# SEV-Remote-Control.net
KiCad netlist of a schematic drawn in EAGLE
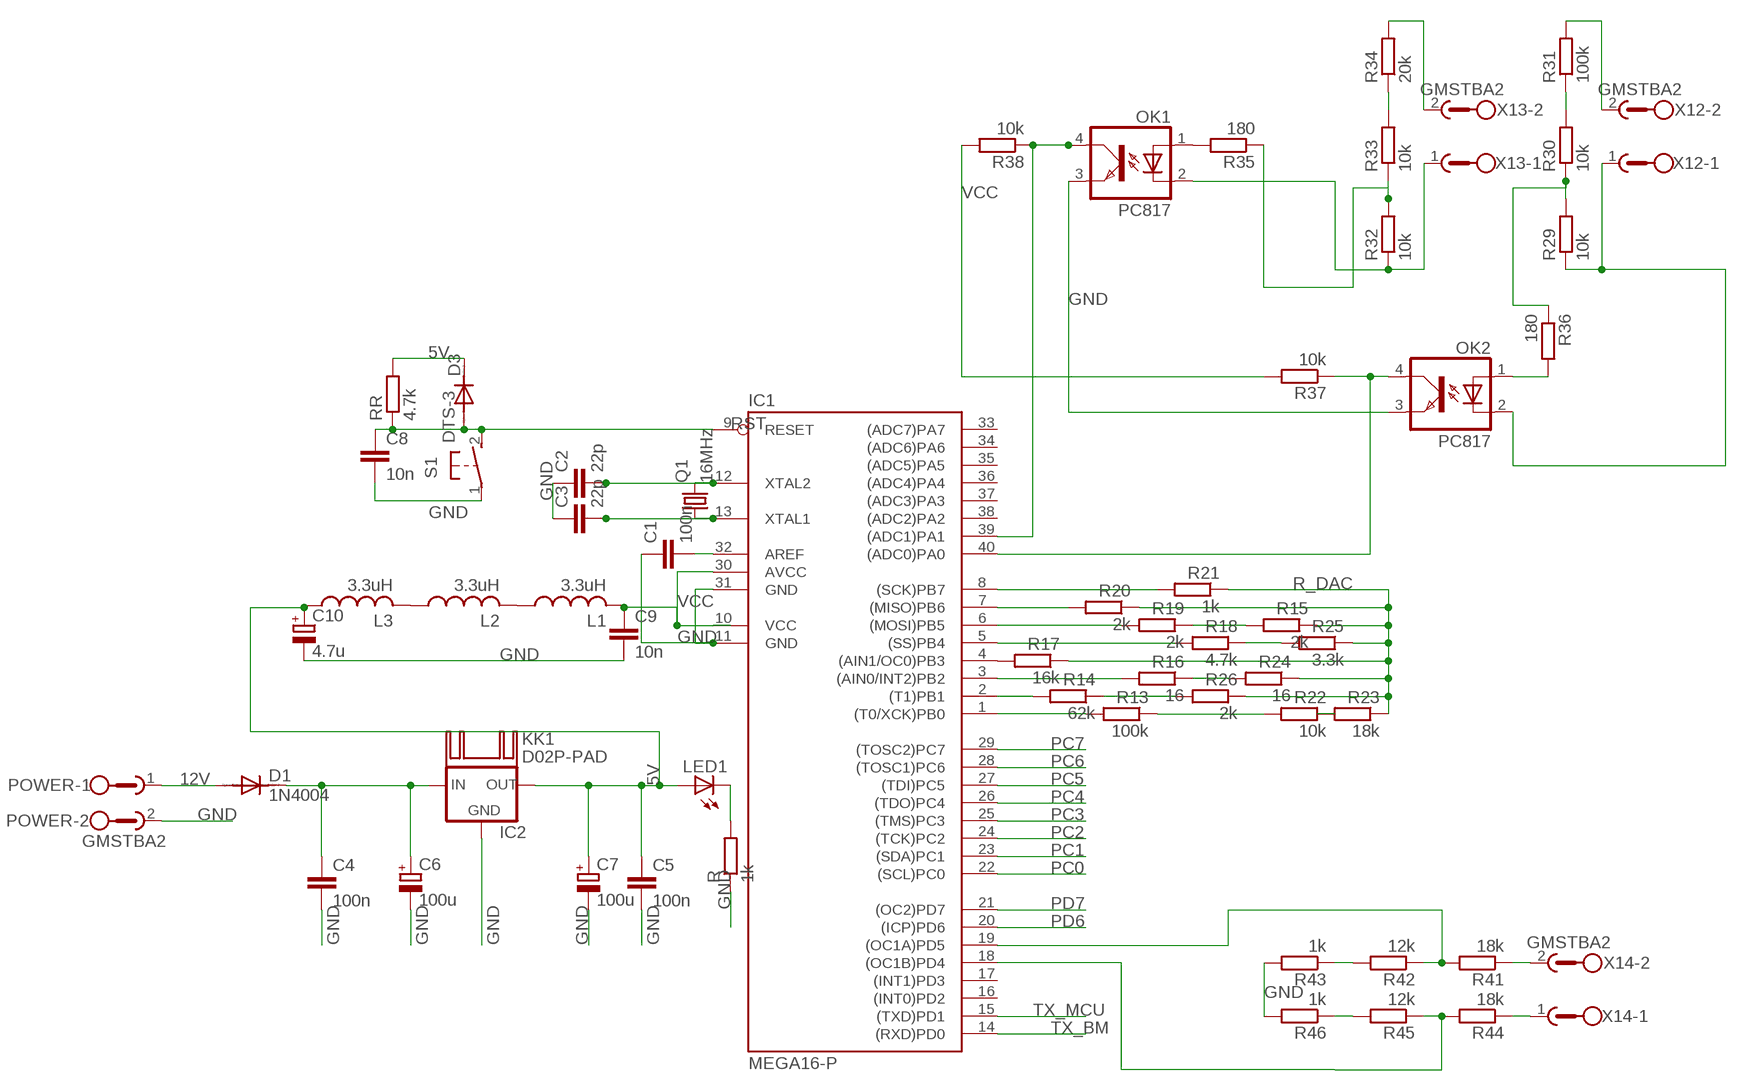
[diagram p0: schematic, sheet 1]
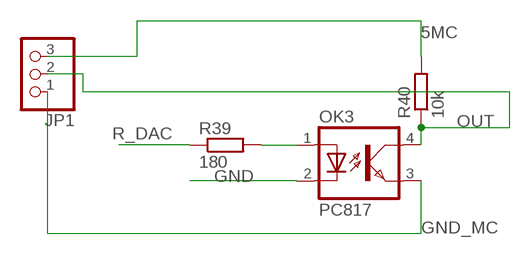
[diagram p1: schematic, sheet 2]
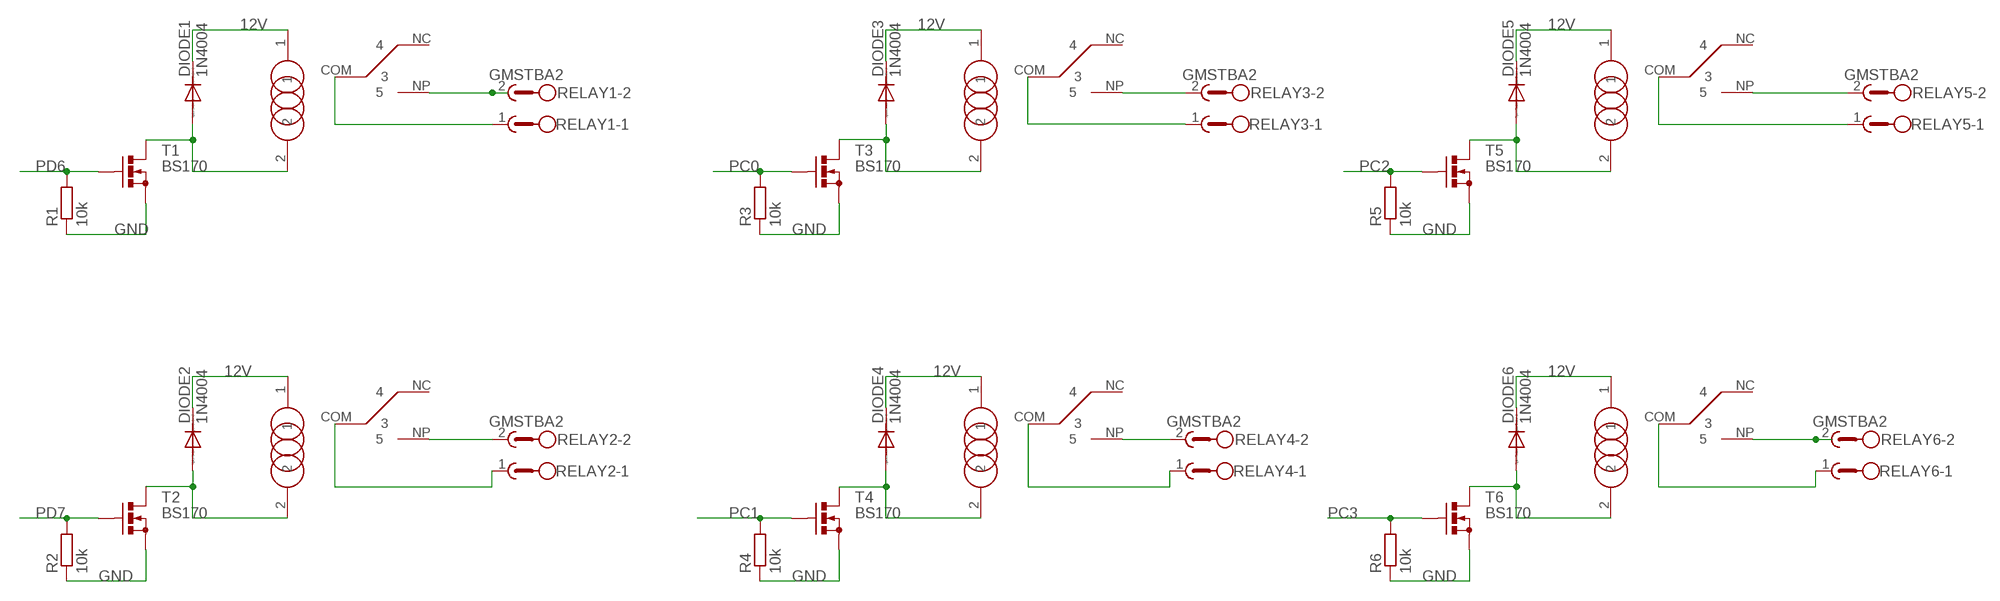
[diagram p2: schematic, sheet 3, part 1 of 2]
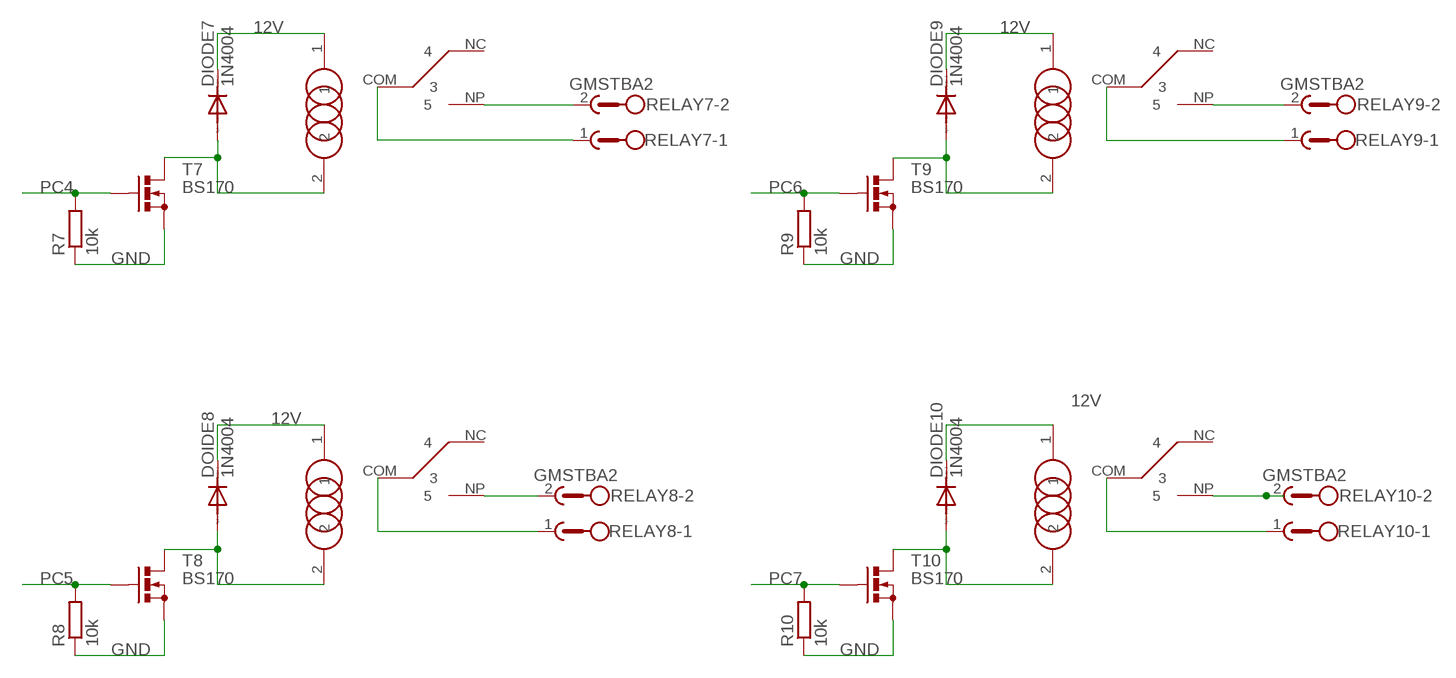
[diagram p3: schematic, sheet 3, part 2 of 2]
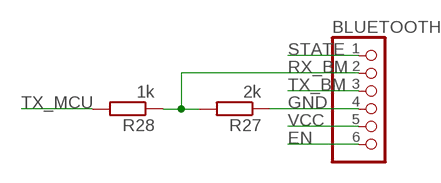
[diagram p4: schematic, sheet 4]

(export (version "E")
  (design (tool "Eeschema 10.0.6"))
  (components
    (comp (ref "C1")
      (value "100n")
      (footprint "eagle-import:C025-025X050")
      (libsource (lib "eagle-import") (part "C-EU025-025X050"))
    )
    (comp (ref "C2")
      (value "22p")
      (footprint "eagle-import:C025-025X050")
      (libsource (lib "eagle-import") (part "C-EU025-025X050"))
    )
    (comp (ref "C3")
      (value "22p")
      (footprint "eagle-import:C025-025X050")
      (libsource (lib "eagle-import") (part "C-EU025-025X050"))
    )
    (comp (ref "C4")
      (value "100n")
      (footprint "eagle-import:C025-025X050")
      (libsource (lib "eagle-import") (part "C-EU025-025X050"))
    )
    (comp (ref "C5")
      (value "100n")
      (footprint "eagle-import:C025-025X050")
      (libsource (lib "eagle-import") (part "C-EU025-025X050"))
    )
    (comp (ref "C6")
      (value "100u")
      (footprint "eagle-import:E2,5-6")
      (libsource (lib "eagle-import") (part "CPOL-EUE2.5-6"))
    )
    (comp (ref "C7")
      (value "100u")
      (footprint "eagle-import:E2,5-6")
      (libsource (lib "eagle-import") (part "CPOL-EUE2.5-6"))
    )
    (comp (ref "C8")
      (value "10n")
      (footprint "eagle-import:C025-025X050")
      (libsource (lib "eagle-import") (part "C-EU025-025X050"))
    )
    (comp (ref "C9")
      (value "10n")
      (footprint "eagle-import:C025-025X050")
      (libsource (lib "eagle-import") (part "C-EU025-025X050"))
    )
    (comp (ref "C10")
      (value "4.7u")
      (footprint "eagle-import:E2,5-6")
      (libsource (lib "eagle-import") (part "CPOL-EUE2.5-6"))
    )
    (comp (ref "D1")
      (value "1N4004")
      (footprint "eagle-import:DO41-10")
      (libsource (lib "eagle-import") (part "1N4004"))
    )
    (comp (ref "D3")
      (value "1N4148DO35-10")
      (footprint "eagle-import:DO35-10")
      (libsource (lib "eagle-import") (part "1N4148DO35-10"))
    )
    (comp (ref "IC1")
      (value "MEGA16-P")
      (footprint "eagle-import:DIL40")
      (fields (field (name "MPN") "ATMEGA16-16PU"))
      (libsource (lib "eagle-import") (part "MEGA16-P"))
    )
    (comp (ref "IC2")
      (value "78XXS")
      (footprint "eagle-import:78XXS")
      (libsource (lib "eagle-import") (part "78XXS"))
    )
    (comp (ref "KK1")
      (value "D02P-PAD")
      (footprint "eagle-import:D02PA-PAD")
      (libsource (lib "eagle-import") (part "D02P-PAD"))
    )
    (comp (ref "L1")
      (value "3.3uH")
      (footprint "eagle-import:0207_7")
      (libsource (lib "eagle-import") (part "L-US0207/7"))
    )
    (comp (ref "L2")
      (value "3.3uH")
      (footprint "eagle-import:0207_7")
      (libsource (lib "eagle-import") (part "L-US0207/7"))
    )
    (comp (ref "L3")
      (value "3.3uH")
      (footprint "eagle-import:0207_7")
      (libsource (lib "eagle-import") (part "L-US0207/7"))
    )
    (comp (ref "LED1")
      (value "LED5MM")
      (footprint "eagle-import:LED5MM")
      (libsource (lib "eagle-import") (part "LED5MM"))
    )
    (comp (ref "OK1")
      (value "PC817")
      (footprint "eagle-import:DIL04")
      (fields (field (name "MPN") "PC817X4J000F"))
      (libsource (lib "eagle-import") (part "PC817"))
    )
    (comp (ref "OK2")
      (value "PC817")
      (footprint "eagle-import:DIL04")
      (fields (field (name "MPN") "PC817X4J000F"))
      (libsource (lib "eagle-import") (part "PC817"))
    )
    (comp (ref "POWER")
      (value "GMSTBA2")
      (footprint "eagle-import:GMSTBA2")
      (fields (field (name "MF") "FARNELL") (field (name "MPN") "1757242"))
      (libsource (lib "eagle-import") (part "GMSTBA2"))
    )
    (comp (ref "Q1")
      (value "16MHz")
      (footprint "eagle-import:HC49_S")
      (libsource (lib "eagle-import") (part "CRYSTALHC49S"))
    )
    (comp (ref "R")
      (value "1k")
      (footprint "eagle-import:0207_10")
      (libsource (lib "eagle-import") (part "R-EU_0207/10"))
    )
    (comp (ref "R13")
      (value "100k")
      (footprint "eagle-import:0207_10")
      (libsource (lib "eagle-import") (part "R-EU_0207/10"))
    )
    (comp (ref "R14")
      (value "62k")
      (footprint "eagle-import:0207_10")
      (libsource (lib "eagle-import") (part "R-EU_0207/10"))
    )
    (comp (ref "R15")
      (value "2k")
      (footprint "eagle-import:0207_10")
      (libsource (lib "eagle-import") (part "R-EU_0207/10"))
    )
    (comp (ref "R16")
      (value "16")
      (footprint "eagle-import:0207_10")
      (libsource (lib "eagle-import") (part "R-EU_0207/10"))
    )
    (comp (ref "R17")
      (value "16k")
      (footprint "eagle-import:0207_10")
      (libsource (lib "eagle-import") (part "R-EU_0207/10"))
    )
    (comp (ref "R18")
      (value "4.7k")
      (footprint "eagle-import:0207_10")
      (libsource (lib "eagle-import") (part "R-EU_0207/10"))
    )
    (comp (ref "R19")
      (value "2k")
      (footprint "eagle-import:0207_10")
      (libsource (lib "eagle-import") (part "R-EU_0207/10"))
    )
    (comp (ref "R20")
      (value "2k")
      (footprint "eagle-import:0207_10")
      (libsource (lib "eagle-import") (part "R-EU_0207/10"))
    )
    (comp (ref "R21")
      (value "1k")
      (footprint "eagle-import:0207_10")
      (libsource (lib "eagle-import") (part "R-EU_0207/10"))
    )
    (comp (ref "R22")
      (value "10k")
      (footprint "eagle-import:0207_10")
      (libsource (lib "eagle-import") (part "R-EU_0207/10"))
    )
    (comp (ref "R23")
      (value "18k")
      (footprint "eagle-import:0207_10")
      (libsource (lib "eagle-import") (part "R-EU_0207/10"))
    )
    (comp (ref "R24")
      (value "16")
      (footprint "eagle-import:0207_10")
      (libsource (lib "eagle-import") (part "R-EU_0207/10"))
    )
    (comp (ref "R25")
      (value "3.3k")
      (footprint "eagle-import:0207_10")
      (libsource (lib "eagle-import") (part "R-EU_0207/10"))
    )
    (comp (ref "R26")
      (value "2k")
      (footprint "eagle-import:0207_10")
      (libsource (lib "eagle-import") (part "R-EU_0207/10"))
    )
    (comp (ref "R29")
      (value "10k")
      (footprint "eagle-import:0207_10")
      (libsource (lib "eagle-import") (part "R-EU_0207/10"))
    )
    (comp (ref "R30")
      (value "10k")
      (footprint "eagle-import:0207_10")
      (libsource (lib "eagle-import") (part "R-EU_0207/10"))
    )
    (comp (ref "R31")
      (value "100k")
      (footprint "eagle-import:0207_10")
      (libsource (lib "eagle-import") (part "R-EU_0207/10"))
    )
    (comp (ref "R32")
      (value "10k")
      (footprint "eagle-import:0207_10")
      (libsource (lib "eagle-import") (part "R-EU_0207/10"))
    )
    (comp (ref "R33")
      (value "10k")
      (footprint "eagle-import:0207_10")
      (libsource (lib "eagle-import") (part "R-EU_0207/10"))
    )
    (comp (ref "R34")
      (value "20k")
      (footprint "eagle-import:0207_10")
      (libsource (lib "eagle-import") (part "R-EU_0207/10"))
    )
    (comp (ref "R35")
      (value "180")
      (footprint "eagle-import:0207_10")
      (libsource (lib "eagle-import") (part "R-EU_0207/10"))
    )
    (comp (ref "R36")
      (value "180")
      (footprint "eagle-import:0207_10")
      (libsource (lib "eagle-import") (part "R-EU_0207/10"))
    )
    (comp (ref "R37")
      (value "10k")
      (footprint "eagle-import:0207_10")
      (libsource (lib "eagle-import") (part "R-EU_0207/10"))
    )
    (comp (ref "R38")
      (value "10k")
      (footprint "eagle-import:0207_10")
      (libsource (lib "eagle-import") (part "R-EU_0207/10"))
    )
    (comp (ref "R41")
      (value "18k")
      (footprint "eagle-import:0207_10")
      (libsource (lib "eagle-import") (part "R-EU_0207/10"))
    )
    (comp (ref "R42")
      (value "12k")
      (footprint "eagle-import:0207_10")
      (libsource (lib "eagle-import") (part "R-EU_0207/10"))
    )
    (comp (ref "R43")
      (value "1k")
      (footprint "eagle-import:0207_10")
      (libsource (lib "eagle-import") (part "R-EU_0207/10"))
    )
    (comp (ref "R44")
      (value "18k")
      (footprint "eagle-import:0207_10")
      (libsource (lib "eagle-import") (part "R-EU_0207/10"))
    )
    (comp (ref "R45")
      (value "12k")
      (footprint "eagle-import:0207_10")
      (libsource (lib "eagle-import") (part "R-EU_0207/10"))
    )
    (comp (ref "R46")
      (value "1k")
      (footprint "eagle-import:0207_10")
      (libsource (lib "eagle-import") (part "R-EU_0207/10"))
    )
    (comp (ref "RR")
      (value "4.7k")
      (footprint "eagle-import:0207_10")
      (libsource (lib "eagle-import") (part "R-EU_0207/10"))
    )
    (comp (ref "S1")
      (value "DTS-3")
      (footprint "eagle-import:DTS-3")
      (libsource (lib "eagle-import") (part "DTS-3"))
    )
    (comp (ref "X12")
      (value "GMSTBA2")
      (footprint "eagle-import:GMSTBA2")
      (fields (field (name "MF") "FARNELL") (field (name "MPN") "1757242"))
      (libsource (lib "eagle-import") (part "GMSTBA2"))
    )
    (comp (ref "X13")
      (value "GMSTBA2")
      (footprint "eagle-import:GMSTBA2")
      (fields (field (name "MF") "FARNELL") (field (name "MPN") "1757242"))
      (libsource (lib "eagle-import") (part "GMSTBA2"))
    )
    (comp (ref "X14")
      (value "GMSTBA2")
      (footprint "eagle-import:GMSTBA2")
      (fields (field (name "MF") "FARNELL") (field (name "MPN") "1757242"))
      (libsource (lib "eagle-import") (part "GMSTBA2"))
    )
    (comp (ref "BLUETOOTH")
      (value "PINHD-1X6")
      (footprint "eagle-import:1X06")
      (libsource (lib "eagle-import") (part "PINHD-1X6"))
    )
    (comp (ref "R27")
      (value "2k")
      (footprint "eagle-import:0207_10")
      (libsource (lib "eagle-import") (part "R-EU_0207/10"))
    )
    (comp (ref "R28")
      (value "1k")
      (footprint "eagle-import:0207_10")
      (libsource (lib "eagle-import") (part "R-EU_0207/10"))
    )
    (comp (ref "JP1")
      (value "PINHD-1X3")
      (footprint "eagle-import:1X03")
      (libsource (lib "eagle-import") (part "PINHD-1X3"))
    )
    (comp (ref "OK3")
      (value "PC817")
      (footprint "eagle-import:DIL04")
      (fields (field (name "MPN") "PC817X4J000F"))
      (libsource (lib "eagle-import") (part "PC817"))
    )
    (comp (ref "R39")
      (value "180")
      (footprint "eagle-import:0207_10")
      (libsource (lib "eagle-import") (part "R-EU_0207/10"))
    )
    (comp (ref "R40")
      (value "10k")
      (footprint "eagle-import:0207_10")
      (libsource (lib "eagle-import") (part "R-EU_0207/10"))
    )
    (comp (ref "DIODE1")
      (value "1N4004")
      (footprint "eagle-import:DO41-10")
      (libsource (lib "eagle-import") (part "1N4004"))
    )
    (comp (ref "DIODE2")
      (value "1N4004")
      (footprint "eagle-import:DO41-10")
      (libsource (lib "eagle-import") (part "1N4004"))
    )
    (comp (ref "DIODE3")
      (value "1N4004")
      (footprint "eagle-import:DO41-10")
      (libsource (lib "eagle-import") (part "1N4004"))
    )
    (comp (ref "DIODE4")
      (value "1N4004")
      (footprint "eagle-import:DO41-10")
      (libsource (lib "eagle-import") (part "1N4004"))
    )
    (comp (ref "DIODE5")
      (value "1N4004")
      (footprint "eagle-import:DO41-10")
      (libsource (lib "eagle-import") (part "1N4004"))
    )
    (comp (ref "DIODE6")
      (value "1N4004")
      (footprint "eagle-import:DO41-10")
      (libsource (lib "eagle-import") (part "1N4004"))
    )
    (comp (ref "DIODE7")
      (value "1N4004")
      (footprint "eagle-import:DO41-10")
      (libsource (lib "eagle-import") (part "1N4004"))
    )
    (comp (ref "DIODE9")
      (value "1N4004")
      (footprint "eagle-import:DO41-10")
      (libsource (lib "eagle-import") (part "1N4004"))
    )
    (comp (ref "DIODE10")
      (value "1N4004")
      (footprint "eagle-import:DO41-10")
      (libsource (lib "eagle-import") (part "1N4004"))
    )
    (comp (ref "DOIDE8")
      (value "1N4004")
      (footprint "eagle-import:DO41-10")
      (libsource (lib "eagle-import") (part "1N4004"))
    )
    (comp (ref "R1")
      (value "10k")
      (footprint "eagle-import:0207_10")
      (libsource (lib "eagle-import") (part "R-EU_0207/10"))
    )
    (comp (ref "R2")
      (value "10k")
      (footprint "eagle-import:0207_10")
      (libsource (lib "eagle-import") (part "R-EU_0207/10"))
    )
    (comp (ref "R3")
      (value "10k")
      (footprint "eagle-import:0207_10")
      (libsource (lib "eagle-import") (part "R-EU_0207/10"))
    )
    (comp (ref "R4")
      (value "10k")
      (footprint "eagle-import:0207_10")
      (libsource (lib "eagle-import") (part "R-EU_0207/10"))
    )
    (comp (ref "R5")
      (value "10k")
      (footprint "eagle-import:0207_10")
      (libsource (lib "eagle-import") (part "R-EU_0207/10"))
    )
    (comp (ref "R6")
      (value "10k")
      (footprint "eagle-import:0207_10")
      (libsource (lib "eagle-import") (part "R-EU_0207/10"))
    )
    (comp (ref "R7")
      (value "10k")
      (footprint "eagle-import:0207_10")
      (libsource (lib "eagle-import") (part "R-EU_0207/10"))
    )
    (comp (ref "R8")
      (value "10k")
      (footprint "eagle-import:0207_10")
      (libsource (lib "eagle-import") (part "R-EU_0207/10"))
    )
    (comp (ref "R9")
      (value "10k")
      (footprint "eagle-import:0207_10")
      (libsource (lib "eagle-import") (part "R-EU_0207/10"))
    )
    (comp (ref "R10")
      (value "10k")
      (footprint "eagle-import:0207_10")
      (libsource (lib "eagle-import") (part "R-EU_0207/10"))
    )
    (comp (ref "REL3")
      (value "RELAY")
      (footprint "eagle-import:RELAY")
      (libsource (lib "eagle-import") (part "RELAY"))
    )
    (comp (ref "RELAY1")
      (value "GMSTBA2")
      (footprint "eagle-import:GMSTBA2")
      (fields (field (name "MF") "FARNELL") (field (name "MPN") "1757242"))
      (libsource (lib "eagle-import") (part "GMSTBA2"))
    )
    (comp (ref "RELAY2")
      (value "GMSTBA2")
      (footprint "eagle-import:GMSTBA2")
      (fields (field (name "MF") "FARNELL") (field (name "MPN") "1757242"))
      (libsource (lib "eagle-import") (part "GMSTBA2"))
    )
    (comp (ref "RELAY3")
      (value "GMSTBA2")
      (footprint "eagle-import:GMSTBA2")
      (fields (field (name "MF") "FARNELL") (field (name "MPN") "1757242"))
      (libsource (lib "eagle-import") (part "GMSTBA2"))
    )
    (comp (ref "RELAY4")
      (value "GMSTBA2")
      (footprint "eagle-import:GMSTBA2")
      (fields (field (name "MF") "FARNELL") (field (name "MPN") "1757242"))
      (libsource (lib "eagle-import") (part "GMSTBA2"))
    )
    (comp (ref "RELAY5")
      (value "GMSTBA2")
      (footprint "eagle-import:GMSTBA2")
      (fields (field (name "MF") "FARNELL") (field (name "MPN") "1757242"))
      (libsource (lib "eagle-import") (part "GMSTBA2"))
    )
    (comp (ref "RELAY6")
      (value "GMSTBA2")
      (footprint "eagle-import:GMSTBA2")
      (fields (field (name "MF") "FARNELL") (field (name "MPN") "1757242"))
      (libsource (lib "eagle-import") (part "GMSTBA2"))
    )
    (comp (ref "RELAY7")
      (value "GMSTBA2")
      (footprint "eagle-import:GMSTBA2")
      (fields (field (name "MF") "FARNELL") (field (name "MPN") "1757242"))
      (libsource (lib "eagle-import") (part "GMSTBA2"))
    )
    (comp (ref "RELAY8")
      (value "GMSTBA2")
      (footprint "eagle-import:GMSTBA2")
      (fields (field (name "MF") "FARNELL") (field (name "MPN") "1757242"))
      (libsource (lib "eagle-import") (part "GMSTBA2"))
    )
    (comp (ref "RELAY9")
      (value "GMSTBA2")
      (footprint "eagle-import:GMSTBA2")
      (fields (field (name "MF") "FARNELL") (field (name "MPN") "1757242"))
      (libsource (lib "eagle-import") (part "GMSTBA2"))
    )
    (comp (ref "RELAY10")
      (value "GMSTBA2")
      (footprint "eagle-import:GMSTBA2")
      (fields (field (name "MF") "FARNELL") (field (name "MPN") "1757242"))
      (libsource (lib "eagle-import") (part "GMSTBA2"))
    )
    (comp (ref "T1")
      (value "BS170")
      (footprint "eagle-import:SOT54E")
      (libsource (lib "eagle-import") (part "BS170"))
    )
    (comp (ref "T2")
      (value "BS170")
      (footprint "eagle-import:SOT54E")
      (libsource (lib "eagle-import") (part "BS170"))
    )
    (comp (ref "T3")
      (value "BS170")
      (footprint "eagle-import:SOT54E")
      (libsource (lib "eagle-import") (part "BS170"))
    )
    (comp (ref "T4")
      (value "BS170")
      (footprint "eagle-import:SOT54E")
      (libsource (lib "eagle-import") (part "BS170"))
    )
    (comp (ref "T5")
      (value "BS170")
      (footprint "eagle-import:SOT54E")
      (libsource (lib "eagle-import") (part "BS170"))
    )
    (comp (ref "T6")
      (value "BS170")
      (footprint "eagle-import:SOT54E")
      (libsource (lib "eagle-import") (part "BS170"))
    )
    (comp (ref "T7")
      (value "BS170")
      (footprint "eagle-import:SOT54E")
      (libsource (lib "eagle-import") (part "BS170"))
    )
    (comp (ref "T8")
      (value "BS170")
      (footprint "eagle-import:SOT54E")
      (libsource (lib "eagle-import") (part "BS170"))
    )
    (comp (ref "T9")
      (value "BS170")
      (footprint "eagle-import:SOT54E")
      (libsource (lib "eagle-import") (part "BS170"))
    )
    (comp (ref "T10")
      (value "BS170")
      (footprint "eagle-import:SOT54E")
      (libsource (lib "eagle-import") (part "BS170"))
    )
    (comp (ref "U$1")
      (value "RELAY")
      (footprint "eagle-import:RELAY")
      (libsource (lib "eagle-import") (part "RELAY"))
    )
    (comp (ref "U$2")
      (value "RELAY")
      (footprint "eagle-import:RELAY")
      (libsource (lib "eagle-import") (part "RELAY"))
    )
    (comp (ref "U$3")
      (value "RELAY")
      (footprint "eagle-import:RELAY")
      (libsource (lib "eagle-import") (part "RELAY"))
    )
    (comp (ref "U$5")
      (value "RELAY")
      (footprint "eagle-import:RELAY")
      (libsource (lib "eagle-import") (part "RELAY"))
    )
    (comp (ref "U$6")
      (value "RELAY")
      (footprint "eagle-import:RELAY")
      (libsource (lib "eagle-import") (part "RELAY"))
    )
    (comp (ref "U$7")
      (value "RELAY")
      (footprint "eagle-import:RELAY")
      (libsource (lib "eagle-import") (part "RELAY"))
    )
    (comp (ref "U$8")
      (value "RELAY")
      (footprint "eagle-import:RELAY")
      (libsource (lib "eagle-import") (part "RELAY"))
    )
    (comp (ref "U$9")
      (value "RELAY")
      (footprint "eagle-import:RELAY")
      (libsource (lib "eagle-import") (part "RELAY"))
    )
    (comp (ref "U$10")
      (value "RELAY")
      (footprint "eagle-import:RELAY")
      (libsource (lib "eagle-import") (part "RELAY"))
    )
  )
  (nets
    (net (code "1") (name "5MC") (class "Default")
      (node (ref "JP1") (pin "3") (pinfunction "3_3") (pintype "passive"))
      (node (ref "R40") (pin "2") (pinfunction "2_2") (pintype "passive"))
    )
    (net (code "2") (name "5V") (class "Default")
      (node (ref "C10") (pin "+") (pinfunction "+_+") (pintype "passive"))
      (node (ref "C5") (pin "1") (pinfunction "1_1") (pintype "passive"))
      (node (ref "C7") (pin "+") (pinfunction "+_+") (pintype "passive"))
      (node (ref "D3") (pin "C") (pinfunction "C_C") (pintype "passive"))
      (node (ref "IC2") (pin "OUT") (pinfunction "OUT_OUT") (pintype "passive"))
      (node (ref "L3") (pin "1") (pinfunction "1_1") (pintype "passive"))
      (node (ref "LED1") (pin "A") (pinfunction "A_A") (pintype "passive"))
      (node (ref "RR") (pin "2") (pinfunction "2_2") (pintype "passive"))
    )
    (net (code "3") (name "12V") (class "Default")
      (node (ref "D1") (pin "A") (pinfunction "A_A") (pintype "passive"))
      (node (ref "DIODE1") (pin "C") (pinfunction "C_C") (pintype "passive"))
      (node (ref "DIODE10") (pin "C") (pinfunction "C_C") (pintype "passive"))
      (node (ref "DIODE2") (pin "C") (pinfunction "C_C") (pintype "passive"))
      (node (ref "DIODE3") (pin "C") (pinfunction "C_C") (pintype "passive"))
      (node (ref "DIODE4") (pin "C") (pinfunction "C_C") (pintype "passive"))
      (node (ref "DIODE5") (pin "C") (pinfunction "C_C") (pintype "passive"))
      (node (ref "DIODE6") (pin "C") (pinfunction "C_C") (pintype "passive"))
      (node (ref "DIODE7") (pin "C") (pinfunction "C_C") (pintype "passive"))
      (node (ref "DIODE9") (pin "C") (pinfunction "C_C") (pintype "passive"))
      (node (ref "DOIDE8") (pin "C") (pinfunction "C_C") (pintype "passive"))
      (node (ref "POWER") (pin "1") (pinfunction "1_1") (pintype "passive"))
      (node (ref "REL3") (pin "1") (pinfunction "1_1") (pintype "bidirectional"))
      (node (ref "U$1") (pin "1") (pinfunction "1_1") (pintype "bidirectional"))
      (node (ref "U$10") (pin "1") (pinfunction "1_1") (pintype "bidirectional"))
      (node (ref "U$2") (pin "1") (pinfunction "1_1") (pintype "bidirectional"))
      (node (ref "U$3") (pin "1") (pinfunction "1_1") (pintype "bidirectional"))
      (node (ref "U$5") (pin "1") (pinfunction "1_1") (pintype "bidirectional"))
      (node (ref "U$6") (pin "1") (pinfunction "1_1") (pintype "bidirectional"))
      (node (ref "U$7") (pin "1") (pinfunction "1_1") (pintype "bidirectional"))
      (node (ref "U$8") (pin "1") (pinfunction "1_1") (pintype "bidirectional"))
      (node (ref "U$9") (pin "1") (pinfunction "1_1") (pintype "bidirectional"))
    )
    (net (code "4") (name "EN") (class "Default")
      (node (ref "BLUETOOTH") (pin "6") (pinfunction "6_6") (pintype "passive"))
    )
    (net (code "5") (name "GND") (class "Default")
      (node (ref "BLUETOOTH") (pin "4") (pinfunction "4_4") (pintype "passive"))
      (node (ref "C1") (pin "1") (pinfunction "1_1") (pintype "passive"))
      (node (ref "C10") (pin "-") (pinfunction "-_-") (pintype "passive"))
      (node (ref "C2") (pin "1") (pinfunction "1_1") (pintype "passive"))
      (node (ref "C3") (pin "1") (pinfunction "1_1") (pintype "passive"))
      (node (ref "C4") (pin "2") (pinfunction "2_2") (pintype "passive"))
      (node (ref "C5") (pin "2") (pinfunction "2_2") (pintype "passive"))
      (node (ref "C6") (pin "-") (pinfunction "-_-") (pintype "passive"))
      (node (ref "C7") (pin "-") (pinfunction "-_-") (pintype "passive"))
      (node (ref "C8") (pin "2") (pinfunction "2_2") (pintype "passive"))
      (node (ref "C9") (pin "2") (pinfunction "2_2") (pintype "passive"))
      (node (ref "IC1") (pin "11") (pinfunction "GND_11") (pintype "power_in"))
      (node (ref "IC1") (pin "31") (pinfunction "GND_31") (pintype "power_in"))
      (node (ref "IC2") (pin "GND") (pinfunction "GND_GND") (pintype "input"))
      (node (ref "OK1") (pin "3") (pinfunction "EMIT_3") (pintype "passive"))
      (node (ref "OK2") (pin "3") (pinfunction "EMIT_3") (pintype "passive"))
      (node (ref "OK3") (pin "2") (pinfunction "C_2") (pintype "passive"))
      (node (ref "POWER") (pin "2") (pinfunction "1_2") (pintype "passive"))
      (node (ref "R") (pin "1") (pinfunction "1_1") (pintype "passive"))
      (node (ref "R1") (pin "1") (pinfunction "1_1") (pintype "passive"))
      (node (ref "R10") (pin "1") (pinfunction "1_1") (pintype "passive"))
      (node (ref "R2") (pin "1") (pinfunction "1_1") (pintype "passive"))
      (node (ref "R27") (pin "1") (pinfunction "1_1") (pintype "passive"))
      (node (ref "R3") (pin "1") (pinfunction "1_1") (pintype "passive"))
      (node (ref "R4") (pin "1") (pinfunction "1_1") (pintype "passive"))
      (node (ref "R43") (pin "2") (pinfunction "2_2") (pintype "passive"))
      (node (ref "R46") (pin "2") (pinfunction "2_2") (pintype "passive"))
      (node (ref "R5") (pin "1") (pinfunction "1_1") (pintype "passive"))
      (node (ref "R6") (pin "1") (pinfunction "1_1") (pintype "passive"))
      (node (ref "R7") (pin "1") (pinfunction "1_1") (pintype "passive"))
      (node (ref "R8") (pin "1") (pinfunction "1_1") (pintype "passive"))
      (node (ref "R9") (pin "1") (pinfunction "1_1") (pintype "passive"))
      (node (ref "S1") (pin "1") (pinfunction "1_1") (pintype "passive"))
      (node (ref "T1") (pin "S") (pinfunction "S_S") (pintype "passive"))
      (node (ref "T10") (pin "S") (pinfunction "S_S") (pintype "passive"))
      (node (ref "T2") (pin "S") (pinfunction "S_S") (pintype "passive"))
      (node (ref "T3") (pin "S") (pinfunction "S_S") (pintype "passive"))
      (node (ref "T4") (pin "S") (pinfunction "S_S") (pintype "passive"))
      (node (ref "T5") (pin "S") (pinfunction "S_S") (pintype "passive"))
      (node (ref "T6") (pin "S") (pinfunction "S_S") (pintype "passive"))
      (node (ref "T7") (pin "S") (pinfunction "S_S") (pintype "passive"))
      (node (ref "T8") (pin "S") (pinfunction "S_S") (pintype "passive"))
      (node (ref "T9") (pin "S") (pinfunction "S_S") (pintype "passive"))
    )
    (net (code "6") (name "GND_MC") (class "Default")
      (node (ref "JP1") (pin "1") (pinfunction "1_1") (pintype "passive"))
      (node (ref "OK3") (pin "3") (pinfunction "EMIT_3") (pintype "passive"))
    )
    (net (code "7") (name "Net-(C4-Pad1)") (class "Default")
      (node (ref "C4") (pin "1") (pinfunction "1_1") (pintype "passive"))
      (node (ref "C6") (pin "+") (pinfunction "+_+") (pintype "passive"))
      (node (ref "D1") (pin "C") (pinfunction "C_C") (pintype "passive"))
      (node (ref "IC2") (pin "IN") (pinfunction "IN_IN") (pintype "input"))
    )
    (net (code "8") (name "Net-(DIODE1-PadA)") (class "Default")
      (node (ref "DIODE1") (pin "A") (pinfunction "A_A") (pintype "passive"))
      (node (ref "T1") (pin "D") (pinfunction "D_D") (pintype "passive"))
      (node (ref "U$7") (pin "2") (pinfunction "2_2") (pintype "bidirectional"))
    )
    (net (code "9") (name "Net-(DIODE2-PadA)") (class "Default")
      (node (ref "DIODE2") (pin "A") (pinfunction "A_A") (pintype "passive"))
      (node (ref "T2") (pin "D") (pinfunction "D_D") (pintype "passive"))
      (node (ref "U$9") (pin "2") (pinfunction "2_2") (pintype "bidirectional"))
    )
    (net (code "10") (name "Net-(DIODE3-PadA)") (class "Default")
      (node (ref "DIODE3") (pin "A") (pinfunction "A_A") (pintype "passive"))
      (node (ref "REL3") (pin "2") (pinfunction "2_2") (pintype "bidirectional"))
      (node (ref "T3") (pin "D") (pinfunction "D_D") (pintype "passive"))
    )
    (net (code "11") (name "Net-(DIODE4-PadA)") (class "Default")
      (node (ref "DIODE4") (pin "A") (pinfunction "A_A") (pintype "passive"))
      (node (ref "T4") (pin "D") (pinfunction "D_D") (pintype "passive"))
      (node (ref "U$5") (pin "2") (pinfunction "2_2") (pintype "bidirectional"))
    )
    (net (code "12") (name "Net-(DIODE5-PadA)") (class "Default")
      (node (ref "DIODE5") (pin "A") (pinfunction "A_A") (pintype "passive"))
      (node (ref "T5") (pin "D") (pinfunction "D_D") (pintype "passive"))
      (node (ref "U$6") (pin "2") (pinfunction "2_2") (pintype "bidirectional"))
    )
    (net (code "13") (name "Net-(DIODE6-PadA)") (class "Default")
      (node (ref "DIODE6") (pin "A") (pinfunction "A_A") (pintype "passive"))
      (node (ref "T6") (pin "D") (pinfunction "D_D") (pintype "passive"))
      (node (ref "U$8") (pin "2") (pinfunction "2_2") (pintype "bidirectional"))
    )
    (net (code "14") (name "Net-(DIODE7-PadA)") (class "Default")
      (node (ref "DIODE7") (pin "A") (pinfunction "A_A") (pintype "passive"))
      (node (ref "T7") (pin "D") (pinfunction "D_D") (pintype "passive"))
      (node (ref "U$10") (pin "2") (pinfunction "2_2") (pintype "bidirectional"))
    )
    (net (code "15") (name "Net-(DIODE9-PadA)") (class "Default")
      (node (ref "DIODE9") (pin "A") (pinfunction "A_A") (pintype "passive"))
      (node (ref "T9") (pin "D") (pinfunction "D_D") (pintype "passive"))
      (node (ref "U$2") (pin "2") (pinfunction "2_2") (pintype "bidirectional"))
    )
    (net (code "16") (name "Net-(DIODE10-PadA)") (class "Default")
      (node (ref "DIODE10") (pin "A") (pinfunction "A_A") (pintype "passive"))
      (node (ref "T10") (pin "D") (pinfunction "D_D") (pintype "passive"))
      (node (ref "U$3") (pin "2") (pinfunction "2_2") (pintype "bidirectional"))
    )
    (net (code "17") (name "Net-(DOIDE8-PadA)") (class "Default")
      (node (ref "DOIDE8") (pin "A") (pinfunction "A_A") (pintype "passive"))
      (node (ref "T8") (pin "D") (pinfunction "D_D") (pintype "passive"))
      (node (ref "U$1") (pin "2") (pinfunction "2_2") (pintype "bidirectional"))
    )
    (net (code "18") (name "Net-(IC1-(ADC0)PA0)") (class "Default")
      (node (ref "IC1") (pin "40") (pinfunction "(ADC0)PA0_40") (pintype "bidirectional"))
      (node (ref "OK2") (pin "4") (pinfunction "COL_4") (pintype "passive"))
      (node (ref "R37") (pin "1") (pinfunction "1_1") (pintype "passive"))
    )
    (net (code "19") (name "Net-(IC1-(ADC1)PA1)") (class "Default")
      (node (ref "IC1") (pin "39") (pinfunction "(ADC1)PA1_39") (pintype "bidirectional"))
      (node (ref "OK1") (pin "4") (pinfunction "COL_4") (pintype "passive"))
      (node (ref "R38") (pin "1") (pinfunction "1_1") (pintype "passive"))
    )
    (net (code "20") (name "Net-(IC1-(AIN0{slash}INT2)PB2)") (class "Default")
      (node (ref "IC1") (pin "3") (pinfunction "(AIN0/INT2)PB2_3") (pintype "bidirectional"))
      (node (ref "R16") (pin "2") (pinfunction "2_2") (pintype "passive"))
    )
    (net (code "21") (name "Net-(IC1-(AIN1{slash}OC0)PB3)") (class "Default")
      (node (ref "IC1") (pin "4") (pinfunction "(AIN1/OC0)PB3_4") (pintype "bidirectional"))
      (node (ref "R17") (pin "2") (pinfunction "2_2") (pintype "passive"))
    )
    (net (code "22") (name "Net-(IC1-(MISO)PB6)") (class "Default")
      (node (ref "IC1") (pin "7") (pinfunction "(MISO)PB6_7") (pintype "bidirectional"))
      (node (ref "R20") (pin "2") (pinfunction "2_2") (pintype "passive"))
    )
    (net (code "23") (name "Net-(IC1-(MOSI)PB5)") (class "Default")
      (node (ref "IC1") (pin "6") (pinfunction "(MOSI)PB5_6") (pintype "bidirectional"))
      (node (ref "R19") (pin "2") (pinfunction "2_2") (pintype "passive"))
    )
    (net (code "24") (name "Net-(IC1-(OC1A)PD5)") (class "Default")
      (node (ref "IC1") (pin "19") (pinfunction "(OC1A)PD5_19") (pintype "bidirectional"))
      (node (ref "R41") (pin "2") (pinfunction "2_2") (pintype "passive"))
      (node (ref "R42") (pin "1") (pinfunction "1_1") (pintype "passive"))
    )
    (net (code "25") (name "Net-(IC1-(OC1B)PD4)") (class "Default")
      (node (ref "IC1") (pin "18") (pinfunction "(OC1B)PD4_18") (pintype "bidirectional"))
      (node (ref "R44") (pin "2") (pinfunction "2_2") (pintype "passive"))
      (node (ref "R45") (pin "1") (pinfunction "1_1") (pintype "passive"))
    )
    (net (code "26") (name "Net-(IC1-(SCK)PB7)") (class "Default")
      (node (ref "IC1") (pin "8") (pinfunction "(SCK)PB7_8") (pintype "bidirectional"))
      (node (ref "R21") (pin "2") (pinfunction "2_2") (pintype "passive"))
    )
    (net (code "27") (name "Net-(IC1-(SS)PB4)") (class "Default")
      (node (ref "IC1") (pin "5") (pinfunction "(SS)PB4_5") (pintype "bidirectional"))
      (node (ref "R18") (pin "2") (pinfunction "2_2") (pintype "passive"))
    )
    (net (code "28") (name "Net-(IC1-(T0{slash}XCK)PB0)") (class "Default")
      (node (ref "IC1") (pin "1") (pinfunction "(T0/XCK)PB0_1") (pintype "bidirectional"))
      (node (ref "R13") (pin "2") (pinfunction "2_2") (pintype "passive"))
    )
    (net (code "29") (name "Net-(IC1-(T1)PB1)") (class "Default")
      (node (ref "IC1") (pin "2") (pinfunction "(T1)PB1_2") (pintype "bidirectional"))
      (node (ref "R14") (pin "2") (pinfunction "2_2") (pintype "passive"))
    )
    (net (code "30") (name "Net-(IC1-AREF)") (class "Default")
      (node (ref "C1") (pin "2") (pinfunction "2_2") (pintype "passive"))
      (node (ref "IC1") (pin "32") (pinfunction "AREF_32") (pintype "passive"))
    )
    (net (code "31") (name "Net-(IC1-XTAL1)") (class "Default")
      (node (ref "C3") (pin "2") (pinfunction "2_2") (pintype "passive"))
      (node (ref "IC1") (pin "13") (pinfunction "XTAL1_13") (pintype "bidirectional"))
      (node (ref "Q1") (pin "1") (pinfunction "1_1") (pintype "passive"))
    )
    (net (code "32") (name "Net-(IC1-XTAL2)") (class "Default")
      (node (ref "C2") (pin "2") (pinfunction "2_2") (pintype "passive"))
      (node (ref "IC1") (pin "12") (pinfunction "XTAL2_12") (pintype "bidirectional"))
      (node (ref "Q1") (pin "2") (pinfunction "2_2") (pintype "passive"))
    )
    (net (code "33") (name "Net-(L1-Pad1)") (class "Default")
      (node (ref "L1") (pin "1") (pinfunction "1_1") (pintype "passive"))
      (node (ref "L2") (pin "2") (pinfunction "2_2") (pintype "passive"))
    )
    (net (code "34") (name "Net-(L2-Pad1)") (class "Default")
      (node (ref "L2") (pin "1") (pinfunction "1_1") (pintype "passive"))
      (node (ref "L3") (pin "2") (pinfunction "2_2") (pintype "passive"))
    )
    (net (code "35") (name "Net-(LED1-C)") (class "Default")
      (node (ref "LED1") (pin "K") (pinfunction "C_K") (pintype "passive"))
      (node (ref "R") (pin "2") (pinfunction "2_2") (pintype "passive"))
    )
    (net (code "36") (name "Net-(OK1-A)") (class "Default")
      (node (ref "OK1") (pin "1") (pinfunction "A_1") (pintype "passive"))
      (node (ref "R35") (pin "2") (pinfunction "2_2") (pintype "passive"))
    )
    (net (code "37") (name "Net-(OK1-C)") (class "Default")
      (node (ref "OK1") (pin "2") (pinfunction "C_2") (pintype "passive"))
      (node (ref "R32") (pin "1") (pinfunction "1_1") (pintype "passive"))
      (node (ref "X13") (pin "1") (pinfunction "1_1") (pintype "passive"))
    )
    (net (code "38") (name "Net-(OK2-A)") (class "Default")
      (node (ref "OK2") (pin "1") (pinfunction "A_1") (pintype "passive"))
      (node (ref "R36") (pin "2") (pinfunction "2_2") (pintype "passive"))
    )
    (net (code "39") (name "Net-(OK2-C)") (class "Default")
      (node (ref "OK2") (pin "2") (pinfunction "C_2") (pintype "passive"))
      (node (ref "R29") (pin "1") (pinfunction "1_1") (pintype "passive"))
      (node (ref "X12") (pin "1") (pinfunction "1_1") (pintype "passive"))
    )
    (net (code "40") (name "Net-(OK3-A)") (class "Default")
      (node (ref "OK3") (pin "1") (pinfunction "A_1") (pintype "passive"))
      (node (ref "R39") (pin "2") (pinfunction "2_2") (pintype "passive"))
    )
    (net (code "41") (name "Net-(R13-Pad1)") (class "Default")
      (node (ref "R13") (pin "1") (pinfunction "1_1") (pintype "passive"))
      (node (ref "R22") (pin "2") (pinfunction "2_2") (pintype "passive"))
    )
    (net (code "42") (name "Net-(R14-Pad1)") (class "Default")
      (node (ref "R14") (pin "1") (pinfunction "1_1") (pintype "passive"))
      (node (ref "R26") (pin "2") (pinfunction "2_2") (pintype "passive"))
    )
    (net (code "43") (name "Net-(R15-Pad2)") (class "Default")
      (node (ref "R15") (pin "2") (pinfunction "2_2") (pintype "passive"))
      (node (ref "R19") (pin "1") (pinfunction "1_1") (pintype "passive"))
    )
    (net (code "44") (name "Net-(R16-Pad1)") (class "Default")
      (node (ref "R16") (pin "1") (pinfunction "1_1") (pintype "passive"))
      (node (ref "R24") (pin "2") (pinfunction "2_2") (pintype "passive"))
    )
    (net (code "45") (name "Net-(R18-Pad1)") (class "Default")
      (node (ref "R18") (pin "1") (pinfunction "1_1") (pintype "passive"))
      (node (ref "R25") (pin "2") (pinfunction "2_2") (pintype "passive"))
    )
    (net (code "46") (name "Net-(R22-Pad1)") (class "Default")
      (node (ref "R22") (pin "1") (pinfunction "1_1") (pintype "passive"))
      (node (ref "R23") (pin "2") (pinfunction "2_2") (pintype "passive"))
    )
    (net (code "47") (name "Net-(R29-Pad2)") (class "Default")
      (node (ref "R29") (pin "2") (pinfunction "2_2") (pintype "passive"))
      (node (ref "R30") (pin "1") (pinfunction "1_1") (pintype "passive"))
      (node (ref "R36") (pin "1") (pinfunction "1_1") (pintype "passive"))
    )
    (net (code "48") (name "Net-(R30-Pad2)") (class "Default")
      (node (ref "R30") (pin "2") (pinfunction "2_2") (pintype "passive"))
      (node (ref "R31") (pin "1") (pinfunction "1_1") (pintype "passive"))
    )
    (net (code "49") (name "Net-(R32-Pad2)") (class "Default")
      (node (ref "R32") (pin "2") (pinfunction "2_2") (pintype "passive"))
      (node (ref "R33") (pin "1") (pinfunction "1_1") (pintype "passive"))
      (node (ref "R35") (pin "1") (pinfunction "1_1") (pintype "passive"))
    )
    (net (code "50") (name "Net-(R33-Pad2)") (class "Default")
      (node (ref "R33") (pin "2") (pinfunction "2_2") (pintype "passive"))
      (node (ref "R34") (pin "1") (pinfunction "1_1") (pintype "passive"))
    )
    (net (code "51") (name "Net-(R42-Pad2)") (class "Default")
      (node (ref "R42") (pin "2") (pinfunction "2_2") (pintype "passive"))
      (node (ref "R43") (pin "1") (pinfunction "1_1") (pintype "passive"))
    )
    (net (code "52") (name "Net-(R44-Pad1)") (class "Default")
      (node (ref "R44") (pin "1") (pinfunction "1_1") (pintype "passive"))
      (node (ref "X14") (pin "1") (pinfunction "1_1") (pintype "passive"))
    )
    (net (code "53") (name "Net-(R45-Pad2)") (class "Default")
      (node (ref "R45") (pin "2") (pinfunction "2_2") (pintype "passive"))
      (node (ref "R46") (pin "1") (pinfunction "1_1") (pintype "passive"))
    )
    (net (code "54") (name "Net-(REL3-3)") (class "Default")
      (node (ref "REL3") (pin "COM") (pinfunction "3_COM") (pintype "bidirectional"))
      (node (ref "RELAY3") (pin "1") (pinfunction "1_1") (pintype "passive"))
    )
    (net (code "55") (name "Net-(REL3-5)") (class "Default")
      (node (ref "REL3") (pin "NP") (pinfunction "5_NP") (pintype "bidirectional"))
      (node (ref "RELAY3") (pin "2") (pinfunction "1_2") (pintype "passive"))
    )
    (net (code "56") (name "Net-(RELAY1B-1)") (class "Default")
      (node (ref "RELAY1") (pin "2") (pinfunction "1_2") (pintype "passive"))
      (node (ref "U$7") (pin "NP") (pinfunction "5_NP") (pintype "bidirectional"))
    )
    (net (code "57") (name "Net-(RELAY2B-1)") (class "Default")
      (node (ref "RELAY2") (pin "2") (pinfunction "1_2") (pintype "passive"))
      (node (ref "U$9") (pin "NP") (pinfunction "5_NP") (pintype "bidirectional"))
    )
    (net (code "58") (name "Net-(RELAY4B-1)") (class "Default")
      (node (ref "RELAY4") (pin "2") (pinfunction "1_2") (pintype "passive"))
      (node (ref "U$5") (pin "NP") (pinfunction "5_NP") (pintype "bidirectional"))
    )
    (net (code "59") (name "Net-(RELAY5B-1)") (class "Default")
      (node (ref "RELAY5") (pin "2") (pinfunction "1_2") (pintype "passive"))
      (node (ref "U$6") (pin "NP") (pinfunction "5_NP") (pintype "bidirectional"))
    )
    (net (code "60") (name "Net-(RELAY6B-1)") (class "Default")
      (node (ref "RELAY6") (pin "2") (pinfunction "1_2") (pintype "passive"))
      (node (ref "U$8") (pin "NP") (pinfunction "5_NP") (pintype "bidirectional"))
    )
    (net (code "61") (name "Net-(RELAY7B-1)") (class "Default")
      (node (ref "RELAY7") (pin "2") (pinfunction "1_2") (pintype "passive"))
      (node (ref "U$10") (pin "NP") (pinfunction "5_NP") (pintype "bidirectional"))
    )
    (net (code "62") (name "Net-(RELAY8B-1)") (class "Default")
      (node (ref "RELAY8") (pin "2") (pinfunction "1_2") (pintype "passive"))
      (node (ref "U$1") (pin "NP") (pinfunction "5_NP") (pintype "bidirectional"))
    )
    (net (code "63") (name "Net-(RELAY9B-1)") (class "Default")
      (node (ref "RELAY9") (pin "2") (pinfunction "1_2") (pintype "passive"))
      (node (ref "U$2") (pin "NP") (pinfunction "5_NP") (pintype "bidirectional"))
    )
    (net (code "64") (name "Net-(RELAY10B-1)") (class "Default")
      (node (ref "RELAY10") (pin "2") (pinfunction "1_2") (pintype "passive"))
      (node (ref "U$3") (pin "NP") (pinfunction "5_NP") (pintype "bidirectional"))
    )
    (net (code "65") (name "Net-(U$1-3)") (class "Default")
      (node (ref "RELAY8") (pin "1") (pinfunction "1_1") (pintype "passive"))
      (node (ref "U$1") (pin "COM") (pinfunction "3_COM") (pintype "bidirectional"))
    )
    (net (code "66") (name "Net-(U$2-3)") (class "Default")
      (node (ref "RELAY9") (pin "1") (pinfunction "1_1") (pintype "passive"))
      (node (ref "U$2") (pin "COM") (pinfunction "3_COM") (pintype "bidirectional"))
    )
    (net (code "67") (name "Net-(U$3-3)") (class "Default")
      (node (ref "RELAY10") (pin "1") (pinfunction "1_1") (pintype "passive"))
      (node (ref "U$3") (pin "COM") (pinfunction "3_COM") (pintype "bidirectional"))
    )
    (net (code "68") (name "Net-(U$5-3)") (class "Default")
      (node (ref "RELAY4") (pin "1") (pinfunction "1_1") (pintype "passive"))
      (node (ref "U$5") (pin "COM") (pinfunction "3_COM") (pintype "bidirectional"))
    )
    (net (code "69") (name "Net-(U$6-3)") (class "Default")
      (node (ref "RELAY5") (pin "1") (pinfunction "1_1") (pintype "passive"))
      (node (ref "U$6") (pin "COM") (pinfunction "3_COM") (pintype "bidirectional"))
    )
    (net (code "70") (name "Net-(U$7-3)") (class "Default")
      (node (ref "RELAY1") (pin "1") (pinfunction "1_1") (pintype "passive"))
      (node (ref "U$7") (pin "COM") (pinfunction "3_COM") (pintype "bidirectional"))
    )
    (net (code "71") (name "Net-(U$8-3)") (class "Default")
      (node (ref "RELAY6") (pin "1") (pinfunction "1_1") (pintype "passive"))
      (node (ref "U$8") (pin "COM") (pinfunction "3_COM") (pintype "bidirectional"))
    )
    (net (code "72") (name "Net-(U$9-3)") (class "Default")
      (node (ref "RELAY2") (pin "1") (pinfunction "1_1") (pintype "passive"))
      (node (ref "U$9") (pin "COM") (pinfunction "3_COM") (pintype "bidirectional"))
    )
    (net (code "73") (name "Net-(U$10-3)") (class "Default")
      (node (ref "RELAY7") (pin "1") (pinfunction "1_1") (pintype "passive"))
      (node (ref "U$10") (pin "COM") (pinfunction "3_COM") (pintype "bidirectional"))
    )
    (net (code "74") (name "Net-(X12B-1)") (class "Default")
      (node (ref "R31") (pin "2") (pinfunction "2_2") (pintype "passive"))
      (node (ref "X12") (pin "2") (pinfunction "1_2") (pintype "passive"))
    )
    (net (code "75") (name "Net-(X13B-1)") (class "Default")
      (node (ref "R34") (pin "2") (pinfunction "2_2") (pintype "passive"))
      (node (ref "X13") (pin "2") (pinfunction "1_2") (pintype "passive"))
    )
    (net (code "76") (name "Net-(X14B-1)") (class "Default")
      (node (ref "R41") (pin "1") (pinfunction "1_1") (pintype "passive"))
      (node (ref "X14") (pin "2") (pinfunction "1_2") (pintype "passive"))
    )
    (net (code "77") (name "OUT") (class "Default")
      (node (ref "JP1") (pin "2") (pinfunction "2_2") (pintype "passive"))
      (node (ref "OK3") (pin "4") (pinfunction "COL_4") (pintype "passive"))
      (node (ref "R40") (pin "1") (pinfunction "1_1") (pintype "passive"))
    )
    (net (code "78") (name "PC0") (class "Default")
      (node (ref "IC1") (pin "22") (pinfunction "(SCL)PC0_22") (pintype "bidirectional"))
      (node (ref "R3") (pin "2") (pinfunction "2_2") (pintype "passive"))
      (node (ref "T3") (pin "G") (pinfunction "G_G") (pintype "passive"))
    )
    (net (code "79") (name "PC1") (class "Default")
      (node (ref "IC1") (pin "23") (pinfunction "(SDA)PC1_23") (pintype "bidirectional"))
      (node (ref "R4") (pin "2") (pinfunction "2_2") (pintype "passive"))
      (node (ref "T4") (pin "G") (pinfunction "G_G") (pintype "passive"))
    )
    (net (code "80") (name "PC2") (class "Default")
      (node (ref "IC1") (pin "24") (pinfunction "(TCK)PC2_24") (pintype "bidirectional"))
      (node (ref "R5") (pin "2") (pinfunction "2_2") (pintype "passive"))
      (node (ref "T5") (pin "G") (pinfunction "G_G") (pintype "passive"))
    )
    (net (code "81") (name "PC3") (class "Default")
      (node (ref "IC1") (pin "25") (pinfunction "(TMS)PC3_25") (pintype "bidirectional"))
      (node (ref "R6") (pin "2") (pinfunction "2_2") (pintype "passive"))
      (node (ref "T6") (pin "G") (pinfunction "G_G") (pintype "passive"))
    )
    (net (code "82") (name "PC4") (class "Default")
      (node (ref "IC1") (pin "26") (pinfunction "(TDO)PC4_26") (pintype "bidirectional"))
      (node (ref "R7") (pin "2") (pinfunction "2_2") (pintype "passive"))
      (node (ref "T7") (pin "G") (pinfunction "G_G") (pintype "passive"))
    )
    (net (code "83") (name "PC5") (class "Default")
      (node (ref "IC1") (pin "27") (pinfunction "(TDI)PC5_27") (pintype "bidirectional"))
      (node (ref "R8") (pin "2") (pinfunction "2_2") (pintype "passive"))
      (node (ref "T8") (pin "G") (pinfunction "G_G") (pintype "passive"))
    )
    (net (code "84") (name "PC6") (class "Default")
      (node (ref "IC1") (pin "28") (pinfunction "(TOSC1)PC6_28") (pintype "bidirectional"))
      (node (ref "R9") (pin "2") (pinfunction "2_2") (pintype "passive"))
      (node (ref "T9") (pin "G") (pinfunction "G_G") (pintype "passive"))
    )
    (net (code "85") (name "PC7") (class "Default")
      (node (ref "IC1") (pin "29") (pinfunction "(TOSC2)PC7_29") (pintype "bidirectional"))
      (node (ref "R10") (pin "2") (pinfunction "2_2") (pintype "passive"))
      (node (ref "T10") (pin "G") (pinfunction "G_G") (pintype "passive"))
    )
    (net (code "86") (name "PD6") (class "Default")
      (node (ref "IC1") (pin "20") (pinfunction "(ICP)PD6_20") (pintype "bidirectional"))
      (node (ref "R1") (pin "2") (pinfunction "2_2") (pintype "passive"))
      (node (ref "T1") (pin "G") (pinfunction "G_G") (pintype "passive"))
    )
    (net (code "87") (name "PD7") (class "Default")
      (node (ref "IC1") (pin "21") (pinfunction "(OC2)PD7_21") (pintype "bidirectional"))
      (node (ref "R2") (pin "2") (pinfunction "2_2") (pintype "passive"))
      (node (ref "T2") (pin "G") (pinfunction "G_G") (pintype "passive"))
    )
    (net (code "88") (name "RST") (class "Default")
      (node (ref "C8") (pin "1") (pinfunction "1_1") (pintype "passive"))
      (node (ref "D3") (pin "A") (pinfunction "A_A") (pintype "passive"))
      (node (ref "IC1") (pin "9") (pinfunction "RESET_9") (pintype "input"))
      (node (ref "RR") (pin "1") (pinfunction "1_1") (pintype "passive"))
      (node (ref "S1") (pin "2") (pinfunction "2_2") (pintype "passive"))
    )
    (net (code "89") (name "RX_BM") (class "Default")
      (node (ref "BLUETOOTH") (pin "2") (pinfunction "2_2") (pintype "passive"))
      (node (ref "R27") (pin "2") (pinfunction "2_2") (pintype "passive"))
      (node (ref "R28") (pin "1") (pinfunction "1_1") (pintype "passive"))
    )
    (net (code "90") (name "R_DAC") (class "Default")
      (node (ref "R15") (pin "1") (pinfunction "1_1") (pintype "passive"))
      (node (ref "R17") (pin "1") (pinfunction "1_1") (pintype "passive"))
      (node (ref "R20") (pin "1") (pinfunction "1_1") (pintype "passive"))
      (node (ref "R21") (pin "1") (pinfunction "1_1") (pintype "passive"))
      (node (ref "R23") (pin "1") (pinfunction "1_1") (pintype "passive"))
      (node (ref "R24") (pin "1") (pinfunction "1_1") (pintype "passive"))
      (node (ref "R25") (pin "1") (pinfunction "1_1") (pintype "passive"))
      (node (ref "R26") (pin "1") (pinfunction "1_1") (pintype "passive"))
      (node (ref "R39") (pin "1") (pinfunction "1_1") (pintype "passive"))
    )
    (net (code "91") (name "STATE") (class "Default")
      (node (ref "BLUETOOTH") (pin "1") (pinfunction "1_1") (pintype "passive"))
    )
    (net (code "92") (name "TX_BM") (class "Default")
      (node (ref "BLUETOOTH") (pin "3") (pinfunction "3_3") (pintype "passive"))
      (node (ref "IC1") (pin "14") (pinfunction "(RXD)PD0_14") (pintype "bidirectional"))
    )
    (net (code "93") (name "TX_MCU") (class "Default")
      (node (ref "IC1") (pin "15") (pinfunction "(TXD)PD1_15") (pintype "bidirectional"))
      (node (ref "R28") (pin "2") (pinfunction "2_2") (pintype "passive"))
    )
    (net (code "94") (name "VCC") (class "Default")
      (node (ref "BLUETOOTH") (pin "5") (pinfunction "5_5") (pintype "passive"))
      (node (ref "C9") (pin "1") (pinfunction "1_1") (pintype "passive"))
      (node (ref "IC1") (pin "10") (pinfunction "VCC_10") (pintype "power_in"))
      (node (ref "IC1") (pin "30") (pinfunction "AVCC_30") (pintype "power_in"))
      (node (ref "L1") (pin "2") (pinfunction "2_2") (pintype "passive"))
      (node (ref "R37") (pin "2") (pinfunction "2_2") (pintype "passive"))
      (node (ref "R38") (pin "2") (pinfunction "2_2") (pintype "passive"))
    )
    (net (code "95") (name "unconnected-(IC1-(ADC2)PA2-Pad38)") (class "Default")
      (node (ref "IC1") (pin "38") (pinfunction "(ADC2)PA2_38") (pintype "bidirectional"))
    )
    (net (code "96") (name "unconnected-(IC1-(ADC3)PA3-Pad37)") (class "Default")
      (node (ref "IC1") (pin "37") (pinfunction "(ADC3)PA3_37") (pintype "bidirectional"))
    )
    (net (code "97") (name "unconnected-(IC1-(ADC4)PA4-Pad36)") (class "Default")
      (node (ref "IC1") (pin "36") (pinfunction "(ADC4)PA4_36") (pintype "bidirectional"))
    )
    (net (code "98") (name "unconnected-(IC1-(ADC5)PA5-Pad35)") (class "Default")
      (node (ref "IC1") (pin "35") (pinfunction "(ADC5)PA5_35") (pintype "bidirectional"))
    )
    (net (code "99") (name "unconnected-(IC1-(ADC6)PA6-Pad34)") (class "Default")
      (node (ref "IC1") (pin "34") (pinfunction "(ADC6)PA6_34") (pintype "bidirectional"))
    )
    (net (code "100") (name "unconnected-(IC1-(ADC7)PA7-Pad33)") (class "Default")
      (node (ref "IC1") (pin "33") (pinfunction "(ADC7)PA7_33") (pintype "bidirectional"))
    )
    (net (code "101") (name "unconnected-(IC1-(INT0)PD2-Pad16)") (class "Default")
      (node (ref "IC1") (pin "16") (pinfunction "(INT0)PD2_16") (pintype "bidirectional"))
    )
    (net (code "102") (name "unconnected-(IC1-(INT1)PD3-Pad17)") (class "Default")
      (node (ref "IC1") (pin "17") (pinfunction "(INT1)PD3_17") (pintype "bidirectional"))
    )
    (net (code "103") (name "unconnected-(KK1-K-PadB)") (class "Default")
      (node (ref "KK1") (pin "B") (pinfunction "K_B") (pintype "passive"))
    )
    (net (code "104") (name "unconnected-(REL3-4-PadNC)") (class "Default")
      (node (ref "REL3") (pin "NC") (pinfunction "4_NC") (pintype "bidirectional"))
    )
    (net (code "105") (name "unconnected-(U$1-4-PadNC)") (class "Default")
      (node (ref "U$1") (pin "NC") (pinfunction "4_NC") (pintype "bidirectional"))
    )
    (net (code "106") (name "unconnected-(U$2-4-PadNC)") (class "Default")
      (node (ref "U$2") (pin "NC") (pinfunction "4_NC") (pintype "bidirectional"))
    )
    (net (code "107") (name "unconnected-(U$3-4-PadNC)") (class "Default")
      (node (ref "U$3") (pin "NC") (pinfunction "4_NC") (pintype "bidirectional"))
    )
    (net (code "108") (name "unconnected-(U$5-4-PadNC)") (class "Default")
      (node (ref "U$5") (pin "NC") (pinfunction "4_NC") (pintype "bidirectional"))
    )
    (net (code "109") (name "unconnected-(U$6-4-PadNC)") (class "Default")
      (node (ref "U$6") (pin "NC") (pinfunction "4_NC") (pintype "bidirectional"))
    )
    (net (code "110") (name "unconnected-(U$7-4-PadNC)") (class "Default")
      (node (ref "U$7") (pin "NC") (pinfunction "4_NC") (pintype "bidirectional"))
    )
    (net (code "111") (name "unconnected-(U$8-4-PadNC)") (class "Default")
      (node (ref "U$8") (pin "NC") (pinfunction "4_NC") (pintype "bidirectional"))
    )
    (net (code "112") (name "unconnected-(U$9-4-PadNC)") (class "Default")
      (node (ref "U$9") (pin "NC") (pinfunction "4_NC") (pintype "bidirectional"))
    )
    (net (code "113") (name "unconnected-(U$10-4-PadNC)") (class "Default")
      (node (ref "U$10") (pin "NC") (pinfunction "4_NC") (pintype "bidirectional"))
    )
  )
)
